# motorsteuerung.net
KiCad netlist of a schematic drawn in EAGLE
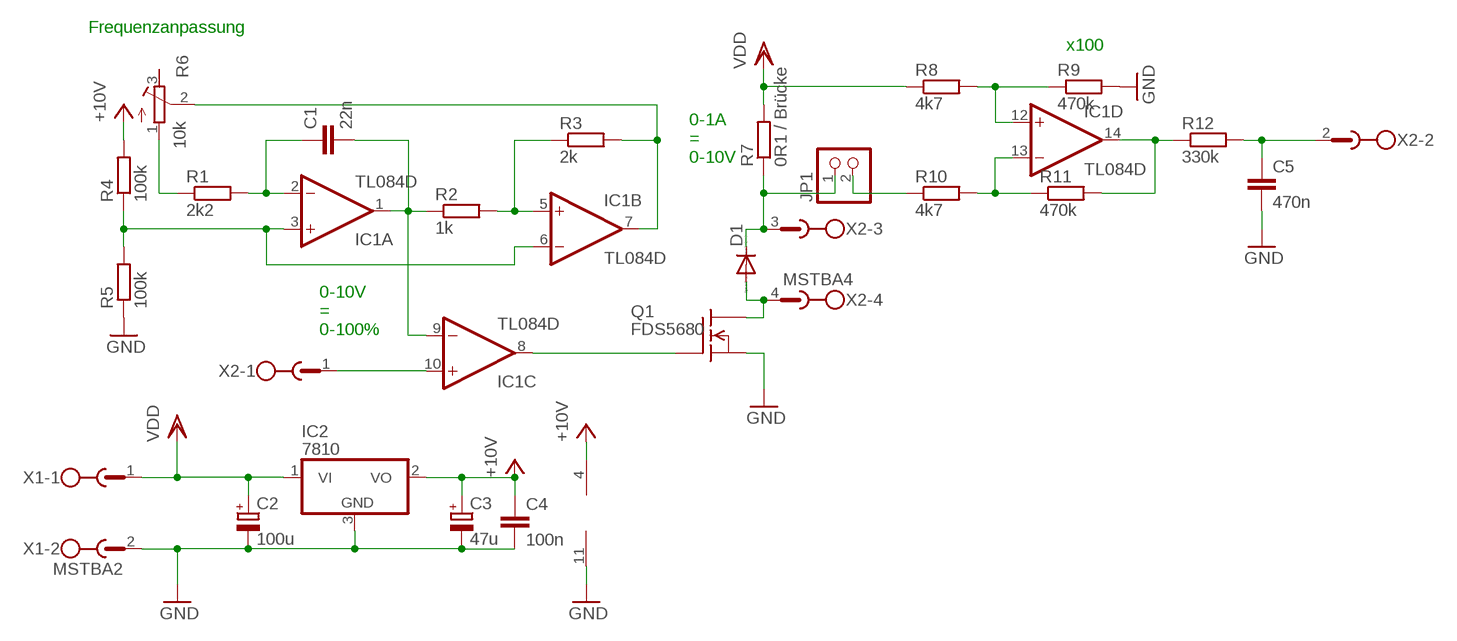
[diagram p0: schematic, sheet 1]

(export (version "E")
  (design (tool "Eeschema 10.0.6"))
  (components
    (comp (ref "C1")
      (value "22n")
      (footprint "eagle-import:C1206")
      (libsource (lib "eagle-import") (part "C-EUC1206"))
    )
    (comp (ref "C2")
      (value "100u")
      (footprint "eagle-import:E3,5-8")
      (libsource (lib "eagle-import") (part "CPOL-EUE3.5-8"))
    )
    (comp (ref "C3")
      (value "47u")
      (footprint "eagle-import:E3,5-8")
      (libsource (lib "eagle-import") (part "CPOL-EUE3.5-8"))
    )
    (comp (ref "C4")
      (value "100n")
      (footprint "eagle-import:C1206")
      (libsource (lib "eagle-import") (part "C-EUC1206"))
    )
    (comp (ref "C5")
      (value "470n")
      (footprint "eagle-import:C1206")
      (libsource (lib "eagle-import") (part "C-EUC1206"))
    )
    (comp (ref "D1")
      (value "1N4148DO35-7")
      (footprint "eagle-import:DO35-7")
      (libsource (lib "eagle-import") (part "1N4148DO35-7"))
    )
    (comp (ref "IC1")
      (value "TL084D")
      (footprint "eagle-import:SO14")
      (libsource (lib "eagle-import") (part "TL084D"))
    )
    (comp (ref "IC2")
      (value "7810")
      (footprint "eagle-import:TO252")
      (libsource (lib "eagle-import") (part "78DT05"))
    )
    (comp (ref "JP1")
      (value "PINHD-1X2")
      (footprint "eagle-import:1X02")
      (libsource (lib "eagle-import") (part "PINHD-1X2"))
    )
    (comp (ref "Q1")
      (value "FDS5680")
      (footprint "eagle-import:SO-8")
      (libsource (lib "eagle-import") (part "FDS5680"))
    )
    (comp (ref "R1")
      (value "2k2")
      (footprint "eagle-import:R1206")
      (libsource (lib "eagle-import") (part "R-EU_R1206"))
    )
    (comp (ref "R2")
      (value "1k")
      (footprint "eagle-import:R1206")
      (libsource (lib "eagle-import") (part "R-EU_R1206"))
    )
    (comp (ref "R3")
      (value "2k")
      (footprint "eagle-import:R1206")
      (libsource (lib "eagle-import") (part "R-EU_R1206"))
    )
    (comp (ref "R4")
      (value "100k")
      (footprint "eagle-import:R1206")
      (libsource (lib "eagle-import") (part "R-EU_R1206"))
    )
    (comp (ref "R5")
      (value "100k")
      (footprint "eagle-import:R1206")
      (libsource (lib "eagle-import") (part "R-EU_R1206"))
    )
    (comp (ref "R6")
      (value "10k")
      (footprint "eagle-import:RTRIM4G_J")
      (libsource (lib "eagle-import") (part "R-TRIMM4G/J"))
    )
    (comp (ref "R7")
      (value "0R1 / Brücke")
      (footprint "eagle-import:R2512")
      (libsource (lib "eagle-import") (part "R-EU_R2512"))
    )
    (comp (ref "R8")
      (value "4k7")
      (footprint "eagle-import:R1206")
      (libsource (lib "eagle-import") (part "R-EU_R1206"))
    )
    (comp (ref "R9")
      (value "470k")
      (footprint "eagle-import:R1206")
      (libsource (lib "eagle-import") (part "R-EU_R1206"))
    )
    (comp (ref "R10")
      (value "4k7")
      (footprint "eagle-import:R1206")
      (libsource (lib "eagle-import") (part "R-EU_R1206"))
    )
    (comp (ref "R11")
      (value "470k")
      (footprint "eagle-import:R1206")
      (libsource (lib "eagle-import") (part "R-EU_R1206"))
    )
    (comp (ref "R12")
      (value "330k")
      (footprint "eagle-import:R1206")
      (libsource (lib "eagle-import") (part "R-EU_R1206"))
    )
    (comp (ref "X1")
      (value "MSTBA2")
      (footprint "eagle-import:MSTBA2")
      (fields (field (name "MF") "FARNELL") (field (name "MPN") "1757242"))
      (libsource (lib "eagle-import") (part "MSTBA2"))
    )
    (comp (ref "X2")
      (value "MSTBA4")
      (footprint "eagle-import:MSTBA4")
      (fields (field (name "MF") "FARNELL") (field (name "MPN") "1757268"))
      (libsource (lib "eagle-import") (part "MSTBA4"))
    )
  )
  (nets
    (net (code "1") (name "+10V") (class "Default")
      (node (ref "C3") (pin "+") (pinfunction "+_+") (pintype "passive"))
      (node (ref "C4") (pin "1") (pinfunction "1_1") (pintype "passive"))
      (node (ref "IC1") (pin "4") (pinfunction "V+_4") (pintype "power_in"))
      (node (ref "IC2") (pin "2") (pinfunction "VO_2") (pintype "passive"))
      (node (ref "R4") (pin "2") (pinfunction "2_2") (pintype "passive"))
    )
    (net (code "2") (name "GND") (class "Default")
      (node (ref "C2") (pin "-") (pinfunction "-_-") (pintype "passive"))
      (node (ref "C3") (pin "-") (pinfunction "-_-") (pintype "passive"))
      (node (ref "C4") (pin "2") (pinfunction "2_2") (pintype "passive"))
      (node (ref "C5") (pin "2") (pinfunction "2_2") (pintype "passive"))
      (node (ref "IC1") (pin "11") (pinfunction "V-_11") (pintype "power_in"))
      (node (ref "IC2") (pin "3") (pinfunction "GND_3") (pintype "passive"))
      (node (ref "Q1") (pin "1") (pinfunction "S_1") (pintype "passive"))
      (node (ref "Q1") (pin "2") (pinfunction "S_2") (pintype "passive"))
      (node (ref "Q1") (pin "3") (pinfunction "S_3") (pintype "passive"))
      (node (ref "R5") (pin "1") (pinfunction "1_1") (pintype "passive"))
      (node (ref "R9") (pin "2") (pinfunction "2_2") (pintype "passive"))
      (node (ref "X1") (pin "2") (pinfunction "1_2") (pintype "passive"))
    )
    (net (code "3") (name "Net-(IC1A-+IN)") (class "Default")
      (node (ref "IC1") (pin "3") (pinfunction "+IN_3") (pintype "input"))
      (node (ref "IC1") (pin "6") (pinfunction "-IN_6") (pintype "input"))
      (node (ref "R4") (pin "1") (pinfunction "1_1") (pintype "passive"))
      (node (ref "R5") (pin "2") (pinfunction "2_2") (pintype "passive"))
    )
    (net (code "4") (name "Net-(IC1A--IN)") (class "Default")
      (node (ref "C1") (pin "1") (pinfunction "1_1") (pintype "passive"))
      (node (ref "IC1") (pin "2") (pinfunction "-IN_2") (pintype "input"))
      (node (ref "R1") (pin "2") (pinfunction "2_2") (pintype "passive"))
    )
    (net (code "5") (name "Net-(IC1A-OUT)") (class "Default")
      (node (ref "C1") (pin "2") (pinfunction "2_2") (pintype "passive"))
      (node (ref "IC1") (pin "1") (pinfunction "OUT_1") (pintype "output"))
      (node (ref "IC1") (pin "9") (pinfunction "-IN_9") (pintype "input"))
      (node (ref "R2") (pin "1") (pinfunction "1_1") (pintype "passive"))
    )
    (net (code "6") (name "Net-(IC1B-+IN)") (class "Default")
      (node (ref "IC1") (pin "5") (pinfunction "+IN_5") (pintype "input"))
      (node (ref "R2") (pin "2") (pinfunction "2_2") (pintype "passive"))
      (node (ref "R3") (pin "1") (pinfunction "1_1") (pintype "passive"))
    )
    (net (code "7") (name "Net-(IC1B-OUT)") (class "Default")
      (node (ref "IC1") (pin "7") (pinfunction "OUT_7") (pintype "output"))
      (node (ref "R3") (pin "2") (pinfunction "2_2") (pintype "passive"))
      (node (ref "R6") (pin "2") (pinfunction "S_2") (pintype "passive"))
    )
    (net (code "8") (name "Net-(IC1C-+IN)") (class "Default")
      (node (ref "IC1") (pin "10") (pinfunction "+IN_10") (pintype "input"))
      (node (ref "X2") (pin "1") (pinfunction "1_1") (pintype "passive"))
    )
    (net (code "9") (name "Net-(IC1C-OUT)") (class "Default")
      (node (ref "IC1") (pin "8") (pinfunction "OUT_8") (pintype "output"))
      (node (ref "Q1") (pin "4") (pinfunction "G_4") (pintype "passive"))
    )
    (net (code "10") (name "Net-(IC1D-+IN)") (class "Default")
      (node (ref "IC1") (pin "12") (pinfunction "+IN_12") (pintype "input"))
      (node (ref "R8") (pin "2") (pinfunction "2_2") (pintype "passive"))
      (node (ref "R9") (pin "1") (pinfunction "1_1") (pintype "passive"))
    )
    (net (code "11") (name "Net-(IC1D--IN)") (class "Default")
      (node (ref "IC1") (pin "13") (pinfunction "-IN_13") (pintype "input"))
      (node (ref "R10") (pin "2") (pinfunction "2_2") (pintype "passive"))
      (node (ref "R11") (pin "1") (pinfunction "1_1") (pintype "passive"))
    )
    (net (code "12") (name "Net-(IC1D-OUT)") (class "Default")
      (node (ref "IC1") (pin "14") (pinfunction "OUT_14") (pintype "output"))
      (node (ref "R11") (pin "2") (pinfunction "2_2") (pintype "passive"))
      (node (ref "R12") (pin "1") (pinfunction "1_1") (pintype "passive"))
    )
    (net (code "13") (name "Net-(JP1-Pad2)") (class "Default")
      (node (ref "JP1") (pin "2") (pinfunction "2_2") (pintype "passive"))
      (node (ref "R10") (pin "1") (pinfunction "1_1") (pintype "passive"))
    )
    (net (code "14") (name "Net-(R6-A)") (class "Default")
      (node (ref "R1") (pin "1") (pinfunction "1_1") (pintype "passive"))
      (node (ref "R6") (pin "1") (pinfunction "A_1") (pintype "passive"))
    )
    (net (code "15") (name "Net-(X2B-1)") (class "Default")
      (node (ref "C5") (pin "1") (pinfunction "1_1") (pintype "passive"))
      (node (ref "R12") (pin "2") (pinfunction "2_2") (pintype "passive"))
      (node (ref "X2") (pin "2") (pinfunction "1_2") (pintype "passive"))
    )
    (net (code "16") (name "Net-(X2C-1)") (class "Default")
      (node (ref "D1") (pin "C") (pinfunction "C_C") (pintype "passive"))
      (node (ref "JP1") (pin "1") (pinfunction "1_1") (pintype "passive"))
      (node (ref "R7") (pin "1") (pinfunction "1_1") (pintype "passive"))
      (node (ref "X2") (pin "3") (pinfunction "1_3") (pintype "passive"))
    )
    (net (code "17") (name "Net-(X2D-1)") (class "Default")
      (node (ref "D1") (pin "A") (pinfunction "A_A") (pintype "passive"))
      (node (ref "Q1") (pin "5") (pinfunction "D_5") (pintype "passive"))
      (node (ref "Q1") (pin "6") (pinfunction "D_6") (pintype "passive"))
      (node (ref "Q1") (pin "7") (pinfunction "D_7") (pintype "passive"))
      (node (ref "Q1") (pin "8") (pinfunction "D_8") (pintype "passive"))
      (node (ref "X2") (pin "4") (pinfunction "1_4") (pintype "passive"))
    )
    (net (code "18") (name "VDD") (class "Default")
      (node (ref "C2") (pin "+") (pinfunction "+_+") (pintype "passive"))
      (node (ref "IC2") (pin "1") (pinfunction "VI_1") (pintype "input"))
      (node (ref "R7") (pin "2") (pinfunction "2_2") (pintype "passive"))
      (node (ref "R8") (pin "1") (pinfunction "1_1") (pintype "passive"))
      (node (ref "X1") (pin "1") (pinfunction "1_1") (pintype "passive"))
    )
    (net (code "19") (name "unconnected-(R6-E-Pad3)") (class "Default")
      (node (ref "R6") (pin "3") (pinfunction "E_3") (pintype "passive"))
    )
  )
)
